# xmega32A4U.net
KiCad netlist of a schematic drawn in EAGLE
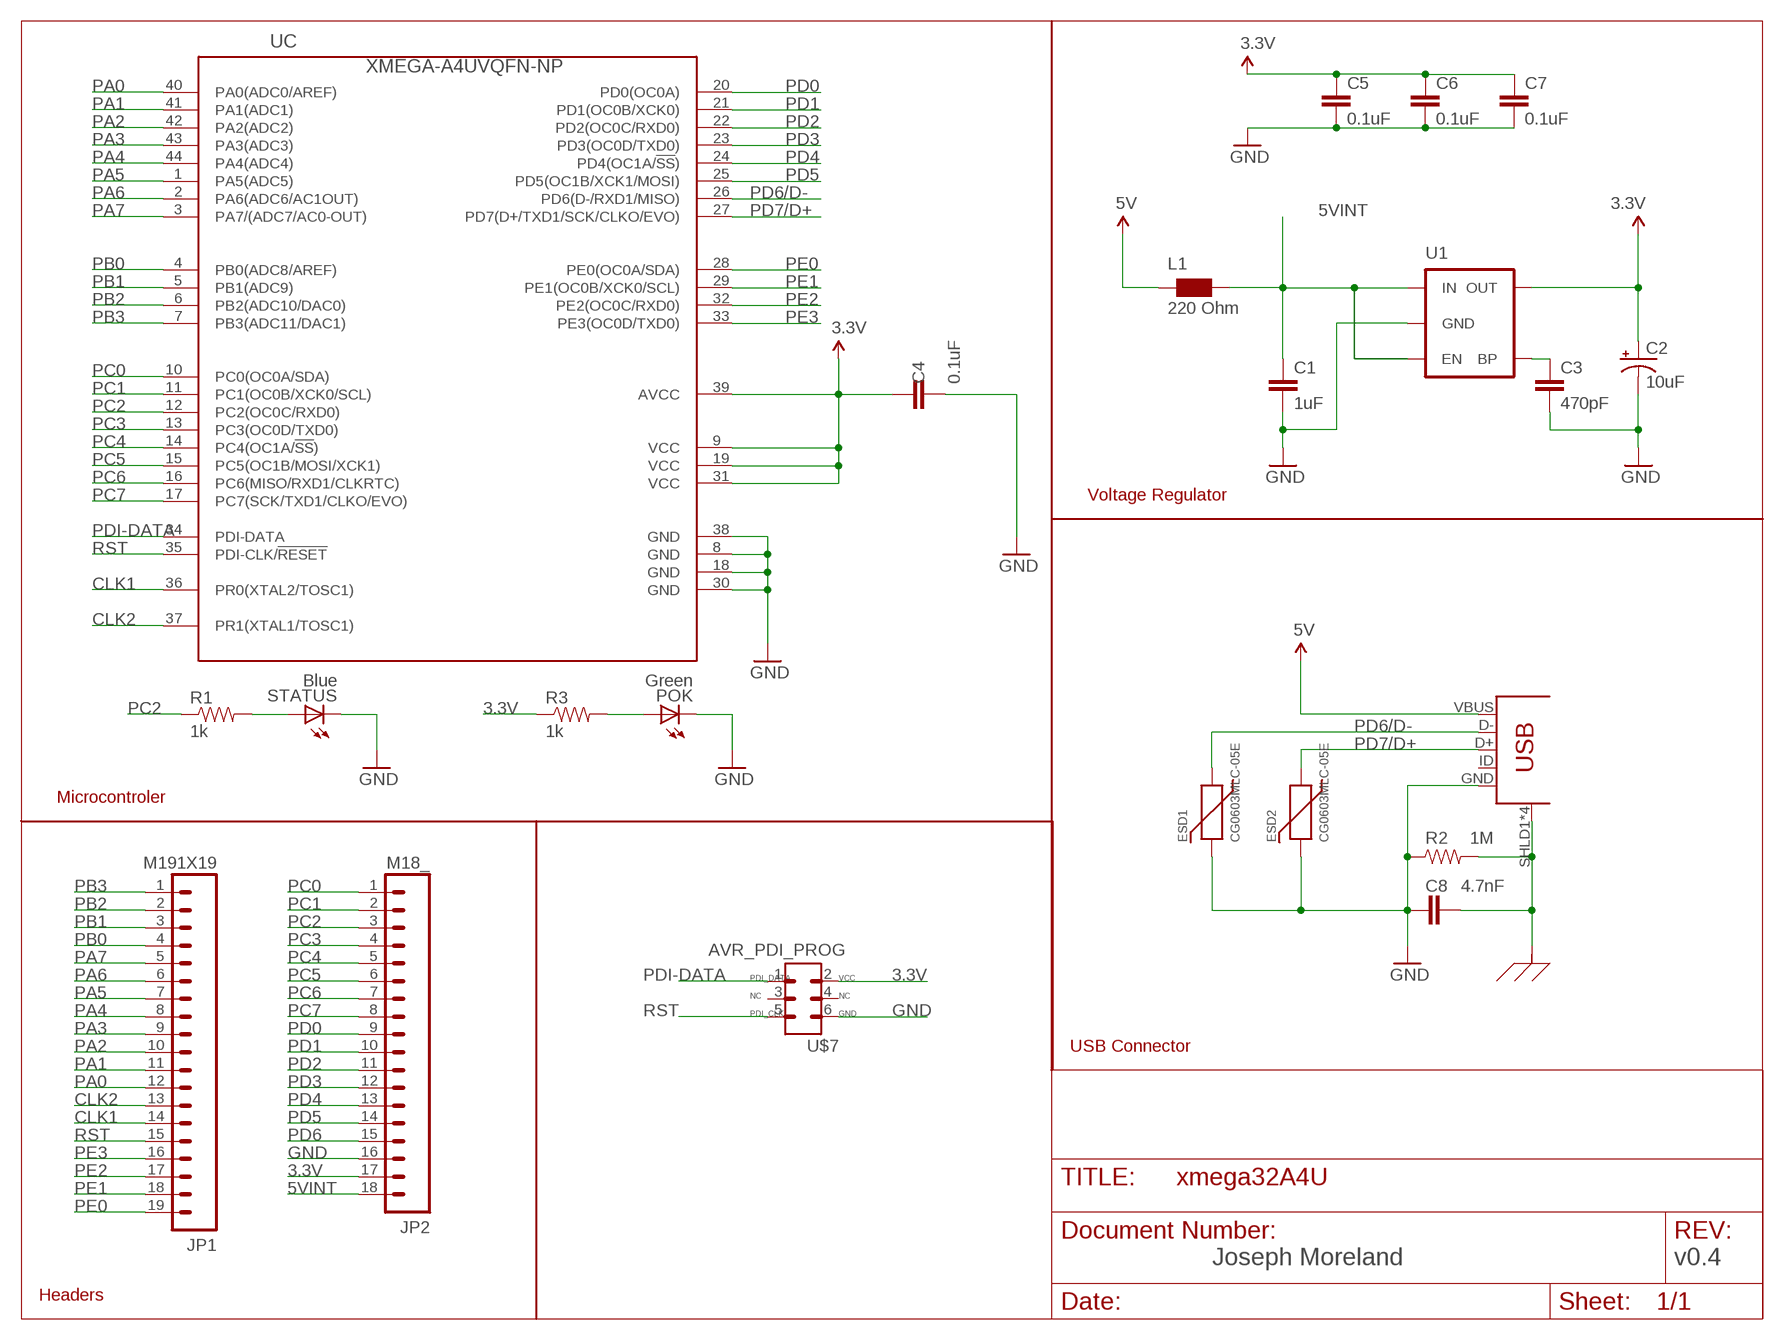
[diagram p0: schematic, sheet 1]

(export (version "E")
  (design (tool "Eeschema 10.0.6"))
  (components
    (comp (ref "C1")
      (value "1uF")
      (footprint "eagle-import:0603-CAP")
      (fields (field (name "PARTNO") "C0603C105K3PACTU"))
      (libsource (lib "eagle-import") (part "CAP0603-CAP"))
    )
    (comp (ref "C2")
      (value "10uF")
      (footprint "eagle-import:EIA3216")
      (fields (field (name "PARTNO") "T494A106M020AT"))
      (libsource (lib "eagle-import") (part "CAP_POL1206"))
    )
    (comp (ref "C3")
      (value "470pF")
      (footprint "eagle-import:0603-CAP")
      (fields (field (name "PARTNO") "C0603C471K5RACTU"))
      (libsource (lib "eagle-import") (part "CAP0603-CAP"))
    )
    (comp (ref "C4")
      (value "0.1uF")
      (footprint "eagle-import:0402-CAP")
      (fields (field (name "PARTNO") "GMK105BJ104KV-F"))
      (libsource (lib "eagle-import") (part "CAP0402-CAP"))
    )
    (comp (ref "C5")
      (value "0.1uF")
      (footprint "eagle-import:0402-CAP")
      (fields (field (name "PARTNO") "GMK105BJ104KV-F"))
      (libsource (lib "eagle-import") (part "CAP0402-CAP"))
    )
    (comp (ref "C6")
      (value "0.1uF")
      (footprint "eagle-import:0402-CAP")
      (fields (field (name "PARTNO") "GMK105BJ104KV-F"))
      (libsource (lib "eagle-import") (part "CAP0402-CAP"))
    )
    (comp (ref "C7")
      (value "0.1uF")
      (footprint "eagle-import:0402-CAP")
      (fields (field (name "PARTNO") "GMK105BJ104KV-F"))
      (libsource (lib "eagle-import") (part "CAP0402-CAP"))
    )
    (comp (ref "C8")
      (value "4.7nF")
      (footprint "eagle-import:0402-CAP")
      (fields (field (name "PARTNO") "C0402C472K3RACTU"))
      (libsource (lib "eagle-import") (part "CAP0402-CAP"))
    )
    (comp (ref "ESD1")
      (value "CG0603MLC-05E")
      (footprint "eagle-import:0603-CHIPGUARD")
      (libsource (lib "eagle-import") (part "CG0603MLC"))
    )
    (comp (ref "ESD2")
      (value "CG0603MLC-05E")
      (footprint "eagle-import:0603-CHIPGUARD")
      (libsource (lib "eagle-import") (part "CG0603MLC"))
    )
    (comp (ref "JP1")
      (value "M191X19")
      (footprint "eagle-import:1X19")
      (fields (field (name "PARTNO") "M20-9732046"))
      (libsource (lib "eagle-import") (part "M191X19"))
    )
    (comp (ref "JP2")
      (value "M18_")
      (footprint "eagle-import:1X18")
      (fields (field (name "PARTNO") "68000-418HLF"))
      (libsource (lib "eagle-import") (part "M18_"))
    )
    (comp (ref "L1")
      (value "220 Ohm")
      (footprint "eagle-import:0603")
      (fields (field (name "PARTNO") "MPZ1608S221A"))
      (libsource (lib "eagle-import") (part "WE-CBF_0603"))
    )
    (comp (ref "POK")
      (value "Green")
      (footprint "eagle-import:LED-0603")
      (fields (field (name "PARTNO") "LTST-C190KGKT"))
      (libsource (lib "eagle-import") (part "LED0603"))
    )
    (comp (ref "R1")
      (value "1k")
      (footprint "eagle-import:0603-RES")
      (fields (field (name "PARTNO") "RC0603FR-071KL"))
      (libsource (lib "eagle-import") (part "RESISTOR0603-RES"))
    )
    (comp (ref "R2")
      (value "1M")
      (footprint "eagle-import:0402-RES")
      (fields (field (name "PARTNO") "CRCW04021M00JNED"))
      (libsource (lib "eagle-import") (part "RESISTOR0402-RES"))
    )
    (comp (ref "R3")
      (value "1k")
      (footprint "eagle-import:0603-RES")
      (fields (field (name "PARTNO") "RC0603FR-071KL"))
      (libsource (lib "eagle-import") (part "RESISTOR0603-RES"))
    )
    (comp (ref "STATUS")
      (value "Blue")
      (footprint "eagle-import:LED-0603")
      (fields (field (name "PARTNO") "LTST-C191TBKT"))
      (libsource (lib "eagle-import") (part "LED0603"))
    )
    (comp (ref "U$4")
      (value "USB-MINIB")
      (footprint "eagle-import:USB-MINI-B-UX60-MB-5S8")
      (fields (field (name "PARTNO") "UX60-MB-5S8"))
      (libsource (lib "eagle-import") (part "USB-MINIB"))
    )
    (comp (ref "U$7")
      (value "AVR_PDI_PROG")
      (footprint "eagle-import:AVR_50MIL_PROG")
      (fields (field (name "PARTNO") "LPPB032NFSP-RC"))
      (libsource (lib "eagle-import") (part "AVR_PDI_PROG"))
    )
    (comp (ref "U1")
      (value "V_REG_MIC52193.3V")
      (footprint "eagle-import:SOT23-5")
      (fields (field (name "PARTNO") "MIC5219-3.3YM5 TR"))
      (libsource (lib "eagle-import") (part "V_REG_MIC52193.3V"))
    )
    (comp (ref "UC")
      (value "XMEGA-A4UVQFN-NP")
      (footprint "eagle-import:QFN44-NOPAD")
      (fields (field (name "PARTNO") "ATXMEGA32A4U-MH"))
      (libsource (lib "eagle-import") (part "XMEGA-A4UVQFN-NP"))
    )
  )
  (nets
    (net (code "1") (name "/5VINT") (class "Default")
      (node (ref "C1") (pin "1") (pinfunction "1_1") (pintype "passive"))
      (node (ref "JP2") (pin "18") (pinfunction "18_18") (pintype "passive"))
      (node (ref "L1") (pin "2") (pinfunction "2_2") (pintype "passive"))
      (node (ref "U1") (pin "1") (pinfunction "IN_1") (pintype "input"))
      (node (ref "U1") (pin "3") (pinfunction "EN_3") (pintype "input"))
    )
    (net (code "2") (name "/CLK1") (class "Default")
      (node (ref "JP1") (pin "14") (pinfunction "14_14") (pintype "passive"))
      (node (ref "UC") (pin "36") (pinfunction "PR0(XTAL2/TOSC1)_36") (pintype "bidirectional"))
    )
    (net (code "3") (name "/CLK2") (class "Default")
      (node (ref "JP1") (pin "13") (pinfunction "13_13") (pintype "passive"))
      (node (ref "UC") (pin "37") (pinfunction "PR1(XTAL1/TOSC1)_37") (pintype "bidirectional"))
    )
    (net (code "4") (name "/PA0") (class "Default")
      (node (ref "JP1") (pin "12") (pinfunction "12_12") (pintype "passive"))
      (node (ref "UC") (pin "40") (pinfunction "PA0(ADC0/AREF)_40") (pintype "bidirectional"))
    )
    (net (code "5") (name "/PA1") (class "Default")
      (node (ref "JP1") (pin "11") (pinfunction "11_11") (pintype "passive"))
      (node (ref "UC") (pin "41") (pinfunction "PA1(ADC1)_41") (pintype "bidirectional"))
    )
    (net (code "6") (name "/PA2") (class "Default")
      (node (ref "JP1") (pin "10") (pinfunction "10_10") (pintype "passive"))
      (node (ref "UC") (pin "42") (pinfunction "PA2(ADC2)_42") (pintype "bidirectional"))
    )
    (net (code "7") (name "/PA3") (class "Default")
      (node (ref "JP1") (pin "9") (pinfunction "9_9") (pintype "passive"))
      (node (ref "UC") (pin "43") (pinfunction "PA3(ADC3)_43") (pintype "bidirectional"))
    )
    (net (code "8") (name "/PA4") (class "Default")
      (node (ref "JP1") (pin "8") (pinfunction "8_8") (pintype "passive"))
      (node (ref "UC") (pin "44") (pinfunction "PA4(ADC4)_44") (pintype "bidirectional"))
    )
    (net (code "9") (name "/PA5") (class "Default")
      (node (ref "JP1") (pin "7") (pinfunction "7_7") (pintype "passive"))
      (node (ref "UC") (pin "1") (pinfunction "PA5(ADC5)_1") (pintype "bidirectional"))
    )
    (net (code "10") (name "/PA6") (class "Default")
      (node (ref "JP1") (pin "6") (pinfunction "6_6") (pintype "passive"))
      (node (ref "UC") (pin "2") (pinfunction "PA6(ADC6/AC1OUT)_2") (pintype "bidirectional"))
    )
    (net (code "11") (name "/PA7") (class "Default")
      (node (ref "JP1") (pin "5") (pinfunction "5_5") (pintype "passive"))
      (node (ref "UC") (pin "3") (pinfunction "PA7/(ADC7/AC0-OUT)_3") (pintype "bidirectional"))
    )
    (net (code "12") (name "/PB0") (class "Default")
      (node (ref "JP1") (pin "4") (pinfunction "4_4") (pintype "passive"))
      (node (ref "UC") (pin "4") (pinfunction "PB0(ADC8/AREF)_4") (pintype "bidirectional"))
    )
    (net (code "13") (name "/PB1") (class "Default")
      (node (ref "JP1") (pin "3") (pinfunction "3_3") (pintype "passive"))
      (node (ref "UC") (pin "5") (pinfunction "PB1(ADC9)_5") (pintype "bidirectional"))
    )
    (net (code "14") (name "/PB2") (class "Default")
      (node (ref "JP1") (pin "2") (pinfunction "2_2") (pintype "passive"))
      (node (ref "UC") (pin "6") (pinfunction "PB2(ADC10/DAC0)_6") (pintype "bidirectional"))
    )
    (net (code "15") (name "/PB3") (class "Default")
      (node (ref "JP1") (pin "1") (pinfunction "1_1") (pintype "passive"))
      (node (ref "UC") (pin "7") (pinfunction "PB3(ADC11/DAC1)_7") (pintype "bidirectional"))
    )
    (net (code "16") (name "/PC0") (class "Default")
      (node (ref "JP2") (pin "1") (pinfunction "1_1") (pintype "passive"))
      (node (ref "UC") (pin "10") (pinfunction "PC0(OC0A/SDA)_10") (pintype "bidirectional"))
    )
    (net (code "17") (name "/PC1") (class "Default")
      (node (ref "JP2") (pin "2") (pinfunction "2_2") (pintype "passive"))
      (node (ref "UC") (pin "11") (pinfunction "PC1(OC0B/XCK0/SCL)_11") (pintype "bidirectional"))
    )
    (net (code "18") (name "/PC2") (class "Default")
      (node (ref "JP2") (pin "3") (pinfunction "3_3") (pintype "passive"))
      (node (ref "R1") (pin "1") (pinfunction "1_1") (pintype "passive"))
      (node (ref "UC") (pin "12") (pinfunction "PC2(OC0C/RXD0)_12") (pintype "bidirectional"))
    )
    (net (code "19") (name "/PC3") (class "Default")
      (node (ref "JP2") (pin "4") (pinfunction "4_4") (pintype "passive"))
      (node (ref "UC") (pin "13") (pinfunction "PC3(OC0D/TXD0)_13") (pintype "bidirectional"))
    )
    (net (code "20") (name "/PC4") (class "Default")
      (node (ref "JP2") (pin "5") (pinfunction "5_5") (pintype "passive"))
      (node (ref "UC") (pin "14") (pinfunction "PC4(OC1A/~{SS})_14") (pintype "bidirectional"))
    )
    (net (code "21") (name "/PC5") (class "Default")
      (node (ref "JP2") (pin "6") (pinfunction "6_6") (pintype "passive"))
      (node (ref "UC") (pin "15") (pinfunction "PC5(OC1B/MOSI/XCK1)_15") (pintype "bidirectional"))
    )
    (net (code "22") (name "/PC6") (class "Default")
      (node (ref "JP2") (pin "7") (pinfunction "7_7") (pintype "passive"))
      (node (ref "UC") (pin "16") (pinfunction "PC6(MISO/RXD1/CLKRTC)_16") (pintype "bidirectional"))
    )
    (net (code "23") (name "/PC7") (class "Default")
      (node (ref "JP2") (pin "8") (pinfunction "8_8") (pintype "passive"))
      (node (ref "UC") (pin "17") (pinfunction "PC7(SCK/TXD1/CLKO/EVO)_17") (pintype "bidirectional"))
    )
    (net (code "24") (name "/PD0") (class "Default")
      (node (ref "JP2") (pin "9") (pinfunction "9_9") (pintype "passive"))
      (node (ref "UC") (pin "20") (pinfunction "PD0(OC0A)_20") (pintype "bidirectional"))
    )
    (net (code "25") (name "/PD1") (class "Default")
      (node (ref "JP2") (pin "10") (pinfunction "10_10") (pintype "passive"))
      (node (ref "UC") (pin "21") (pinfunction "PD1(OC0B/XCK0)_21") (pintype "bidirectional"))
    )
    (net (code "26") (name "/PD2") (class "Default")
      (node (ref "JP2") (pin "11") (pinfunction "11_11") (pintype "passive"))
      (node (ref "UC") (pin "22") (pinfunction "PD2(OC0C/RXD0)_22") (pintype "bidirectional"))
    )
    (net (code "27") (name "/PD3") (class "Default")
      (node (ref "JP2") (pin "12") (pinfunction "12_12") (pintype "passive"))
      (node (ref "UC") (pin "23") (pinfunction "PD3(OC0D/TXD0)_23") (pintype "bidirectional"))
    )
    (net (code "28") (name "/PD4") (class "Default")
      (node (ref "JP2") (pin "13") (pinfunction "13_13") (pintype "passive"))
      (node (ref "UC") (pin "24") (pinfunction "PD4(OC1A/~{SS})_24") (pintype "bidirectional"))
    )
    (net (code "29") (name "/PD5") (class "Default")
      (node (ref "JP2") (pin "14") (pinfunction "14_14") (pintype "passive"))
      (node (ref "UC") (pin "25") (pinfunction "PD5(OC1B/XCK1/MOSI)_25") (pintype "bidirectional"))
    )
    (net (code "30") (name "/PD6") (class "Default")
      (node (ref "JP2") (pin "15") (pinfunction "15_15") (pintype "passive"))
    )
    (net (code "31") (name "/PD6{slash}D-") (class "Default")
      (node (ref "ESD1") (pin "P$2") (pinfunction "P$2_P$2") (pintype "bidirectional"))
      (node (ref "U$4") (pin "D-") (pinfunction "D-_D-") (pintype "bidirectional"))
      (node (ref "UC") (pin "26") (pinfunction "PD6(D-/RXD1/MISO)_26") (pintype "bidirectional"))
    )
    (net (code "32") (name "/PD7{slash}D+") (class "Default")
      (node (ref "ESD2") (pin "P$2") (pinfunction "P$2_P$2") (pintype "bidirectional"))
      (node (ref "U$4") (pin "D+") (pinfunction "D+_D+") (pintype "bidirectional"))
      (node (ref "UC") (pin "27") (pinfunction "PD7(D+/TXD1/SCK/CLKO/EVO)_27") (pintype "bidirectional"))
    )
    (net (code "33") (name "/PDI-DATA") (class "Default")
      (node (ref "U$7") (pin "1") (pinfunction "PDI_DATA_1") (pintype "bidirectional"))
      (node (ref "UC") (pin "34") (pinfunction "PDI-DATA_34") (pintype "bidirectional"))
    )
    (net (code "34") (name "/PE0") (class "Default")
      (node (ref "JP1") (pin "19") (pinfunction "19_19") (pintype "passive"))
      (node (ref "UC") (pin "28") (pinfunction "PE0(OC0A/SDA)_28") (pintype "bidirectional"))
    )
    (net (code "35") (name "/PE1") (class "Default")
      (node (ref "JP1") (pin "18") (pinfunction "18_18") (pintype "passive"))
      (node (ref "UC") (pin "29") (pinfunction "PE1(OC0B/XCK0/SCL)_29") (pintype "bidirectional"))
    )
    (net (code "36") (name "/PE2") (class "Default")
      (node (ref "JP1") (pin "17") (pinfunction "17_17") (pintype "passive"))
      (node (ref "UC") (pin "32") (pinfunction "PE2(OC0C/RXD0)_32") (pintype "bidirectional"))
    )
    (net (code "37") (name "/PE3") (class "Default")
      (node (ref "JP1") (pin "16") (pinfunction "16_16") (pintype "passive"))
      (node (ref "UC") (pin "33") (pinfunction "PE3(OC0D/TXD0)_33") (pintype "bidirectional"))
    )
    (net (code "38") (name "/RST") (class "Default")
      (node (ref "JP1") (pin "15") (pinfunction "15_15") (pintype "passive"))
      (node (ref "U$7") (pin "5") (pinfunction "PDI_CLK_5") (pintype "passive"))
      (node (ref "UC") (pin "35") (pinfunction "PDI-CLK/~{RESET}_35") (pintype "input"))
    )
    (net (code "39") (name "3.3V") (class "Default")
      (node (ref "C2") (pin "A") (pinfunction "+_A") (pintype "passive"))
      (node (ref "C4") (pin "1") (pinfunction "1_1") (pintype "passive"))
      (node (ref "C5") (pin "1") (pinfunction "1_1") (pintype "passive"))
      (node (ref "C6") (pin "1") (pinfunction "1_1") (pintype "passive"))
      (node (ref "C7") (pin "1") (pinfunction "1_1") (pintype "passive"))
      (node (ref "JP2") (pin "17") (pinfunction "17_17") (pintype "passive"))
      (node (ref "R3") (pin "1") (pinfunction "1_1") (pintype "passive"))
      (node (ref "U$7") (pin "2") (pinfunction "VCC_2") (pintype "passive"))
      (node (ref "U1") (pin "5") (pinfunction "OUT_5") (pintype "passive"))
      (node (ref "UC") (pin "19") (pinfunction "VCC_19") (pintype "power_in"))
      (node (ref "UC") (pin "31") (pinfunction "VCC_31") (pintype "power_in"))
      (node (ref "UC") (pin "39") (pinfunction "AVCC_39") (pintype "power_in"))
      (node (ref "UC") (pin "9") (pinfunction "VCC_9") (pintype "power_in"))
    )
    (net (code "40") (name "5V") (class "Default")
      (node (ref "L1") (pin "1") (pinfunction "1_1") (pintype "passive"))
      (node (ref "U$4") (pin "VBUS") (pinfunction "VBUS_VBUS") (pintype "bidirectional"))
    )
    (net (code "41") (name "GND") (class "Default")
      (node (ref "C1") (pin "2") (pinfunction "2_2") (pintype "passive"))
      (node (ref "C2") (pin "C") (pinfunction "-_C") (pintype "passive"))
      (node (ref "C3") (pin "2") (pinfunction "2_2") (pintype "passive"))
      (node (ref "C4") (pin "2") (pinfunction "2_2") (pintype "passive"))
      (node (ref "C5") (pin "2") (pinfunction "2_2") (pintype "passive"))
      (node (ref "C6") (pin "2") (pinfunction "2_2") (pintype "passive"))
      (node (ref "C7") (pin "2") (pinfunction "2_2") (pintype "passive"))
      (node (ref "C8") (pin "1") (pinfunction "1_1") (pintype "passive"))
      (node (ref "ESD1") (pin "P$1") (pinfunction "P$1_P$1") (pintype "bidirectional"))
      (node (ref "ESD2") (pin "P$1") (pinfunction "P$1_P$1") (pintype "bidirectional"))
      (node (ref "JP2") (pin "16") (pinfunction "16_16") (pintype "passive"))
      (node (ref "POK") (pin "C") (pinfunction "C_C") (pintype "passive"))
      (node (ref "R2") (pin "1") (pinfunction "1_1") (pintype "passive"))
      (node (ref "STATUS") (pin "C") (pinfunction "C_C") (pintype "passive"))
      (node (ref "U$4") (pin "GND") (pinfunction "GND_GND") (pintype "bidirectional"))
      (node (ref "U$7") (pin "6") (pinfunction "GND_6") (pintype "passive"))
      (node (ref "U1") (pin "2") (pinfunction "GND_2") (pintype "input"))
      (node (ref "UC") (pin "18") (pinfunction "GND_18") (pintype "power_in"))
      (node (ref "UC") (pin "30") (pinfunction "GND_30") (pintype "power_in"))
      (node (ref "UC") (pin "38") (pinfunction "GND_38") (pintype "power_in"))
      (node (ref "UC") (pin "8") (pinfunction "GND_8") (pintype "power_in"))
    )
    (net (code "42") (name "GND_EARTH") (class "Default")
      (node (ref "C8") (pin "2") (pinfunction "2_2") (pintype "passive"))
      (node (ref "R2") (pin "2") (pinfunction "2_2") (pintype "passive"))
      (node (ref "U$4") (pin "SHLD1") (pinfunction "SHLD_SHLD1") (pintype "bidirectional"))
      (node (ref "U$4") (pin "SHLD2") (pinfunction "SHLD_SHLD2") (pintype "bidirectional"))
      (node (ref "U$4") (pin "SHLD3") (pinfunction "SHLD_SHLD3") (pintype "bidirectional"))
      (node (ref "U$4") (pin "SHLD4") (pinfunction "SHLD_SHLD4") (pintype "bidirectional"))
    )
    (net (code "43") (name "Net-(POK-PadA)") (class "Default")
      (node (ref "POK") (pin "A") (pinfunction "A_A") (pintype "passive"))
      (node (ref "R3") (pin "2") (pinfunction "2_2") (pintype "passive"))
    )
    (net (code "44") (name "Net-(R1-Pad2)") (class "Default")
      (node (ref "R1") (pin "2") (pinfunction "2_2") (pintype "passive"))
      (node (ref "STATUS") (pin "A") (pinfunction "A_A") (pintype "passive"))
    )
    (net (code "45") (name "Net-(U1-BP)") (class "Default")
      (node (ref "C3") (pin "1") (pinfunction "1_1") (pintype "passive"))
      (node (ref "U1") (pin "4") (pinfunction "BP_4") (pintype "input"))
    )
    (net (code "46") (name "unconnected-(U$4-PadID)") (class "Default")
      (node (ref "U$4") (pin "ID") (pinfunction "ID_ID") (pintype "bidirectional"))
    )
    (net (code "47") (name "unconnected-(U$7-NC-Pad3)") (class "Default")
      (node (ref "U$7") (pin "3") (pinfunction "NC_3") (pintype "passive"))
    )
    (net (code "48") (name "unconnected-(U$7-NC1-Pad4)") (class "Default")
      (node (ref "U$7") (pin "4") (pinfunction "NC1_4") (pintype "passive"))
    )
  )
)
